# SCH_USB-PD_Power.net
KiCad netlist of a schematic drawn in Altium Designer
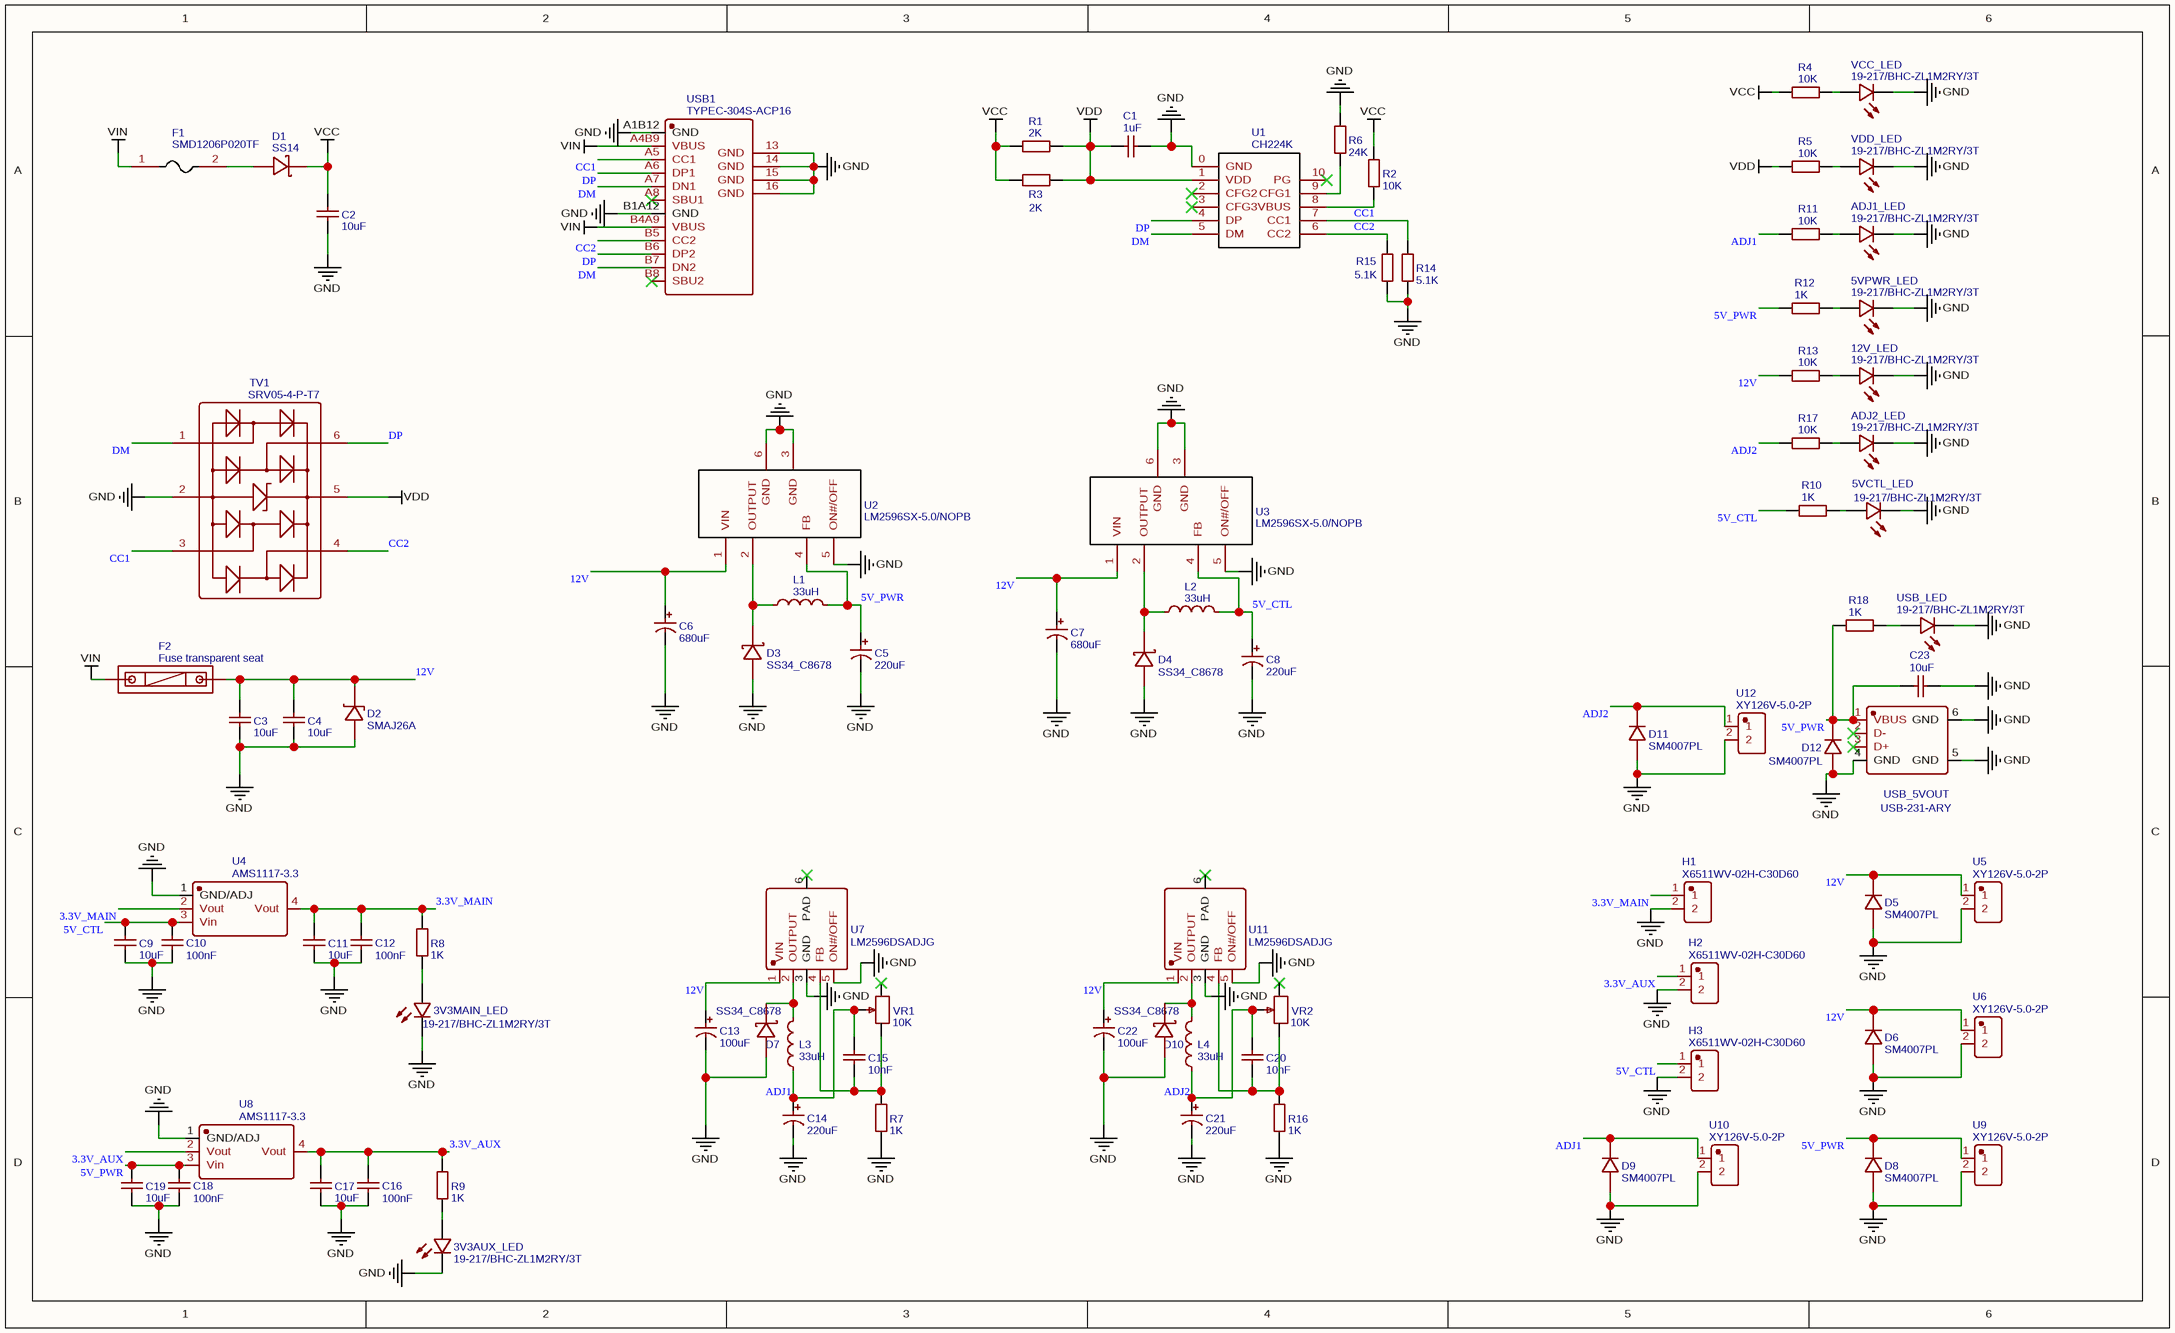
[diagram p0: SCH_USB-PD_Power.schdoc]

(export (version "E")
  (design (tool "Eeschema 10.0.6"))
  (components
    (comp (ref "3V3AUX_LED")
      (value "19-217/BHC-ZL1M2RY/3T")
      (fields (field (name "BOM_SUPPLIER PART") "C72041"))
      (libsource (lib "altium-import") (part "root_1_19-217/BHC-ZL1M2RY/3T_"))
    )
    (comp (ref "3V3MAIN_LED")
      (value "19-217/BHC-ZL1M2RY/3T")
      (fields (field (name "BOM_SUPPLIER PART") "C72041"))
      (libsource (lib "altium-import") (part "root_1_19-217/BHC-ZL1M2RY/3T_"))
    )
    (comp (ref "5VCTL_LED")
      (value "19-217/BHC-ZL1M2RY/3T")
      (fields (field (name "BOM_SUPPLIER PART") "C72041"))
      (libsource (lib "altium-import") (part "root_2_19-217/BHC-ZL1M2RY/3T_"))
    )
    (comp (ref "5VPWR_LED")
      (value "19-217/BHC-ZL1M2RY/3T")
      (fields (field (name "BOM_SUPPLIER PART") "C72041"))
      (libsource (lib "altium-import") (part "root_2_19-217/BHC-ZL1M2RY/3T_"))
    )
    (comp (ref "12V_LED")
      (value "19-217/BHC-ZL1M2RY/3T")
      (fields (field (name "BOM_SUPPLIER PART") "C72041"))
      (libsource (lib "altium-import") (part "root_2_19-217/BHC-ZL1M2RY/3T_"))
    )
    (comp (ref "ADJ1_LED")
      (value "19-217/BHC-ZL1M2RY/3T")
      (fields (field (name "BOM_SUPPLIER PART") "C72041"))
      (libsource (lib "altium-import") (part "root_2_19-217/BHC-ZL1M2RY/3T_"))
    )
    (comp (ref "ADJ2_LED")
      (value "19-217/BHC-ZL1M2RY/3T")
      (fields (field (name "BOM_SUPPLIER PART") "C72041"))
      (libsource (lib "altium-import") (part "root_2_19-217/BHC-ZL1M2RY/3T_"))
    )
    (comp (ref "C1")
      (value "1uF")
      (fields
        (field (name "BOM_MANUFACTURER PART") "CL21B105KBFNNNE")
        (field (name "BOM_SUPPLIER PART") "C28323")
      )
      (libsource (lib "altium-import") (part "root_0_1uF_"))
    )
    (comp (ref "C2")
      (value "10uF")
      (fields
        (field (name "BOM_MANUFACTURER PART") "CL21A106KAYNNNE")
        (field (name "BOM_SUPPLIER PART") "C15850")
      )
      (libsource (lib "altium-import") (part "root_1_10uF_"))
    )
    (comp (ref "C3")
      (value "10uF")
      (fields
        (field (name "BOM_MANUFACTURER PART") "CL21A106KAYNNNE")
        (field (name "BOM_SUPPLIER PART") "C15850")
      )
      (libsource (lib "altium-import") (part "root_1_10uF_"))
    )
    (comp (ref "C4")
      (value "10uF")
      (fields
        (field (name "BOM_MANUFACTURER PART") "CL21A106KAYNNNE")
        (field (name "BOM_SUPPLIER PART") "C15850")
      )
      (libsource (lib "altium-import") (part "root_1_10uF_"))
    )
    (comp (ref "C5")
      (value "220uF")
      (fields (field (name "BOM_MANUFACTURER PART") "220uf/35V") (field (name "BOM_SUPPLIER PART") "C2063"))
      (libsource (lib "altium-import") (part "root_3_220uF_"))
    )
    (comp (ref "C6")
      (value "680uF")
      (fields
        (field (name "BOM_MANUFACTURER PART") "NXA25V680UF10*16")
        (field (name "BOM_SUPPLIER PART") "C150380")
        (field (name "CONTRIBUTOR") "LCSC")
      )
      (libsource (lib "altium-import") (part "root_3_680uF_"))
    )
    (comp (ref "C7")
      (value "680uF")
      (fields
        (field (name "BOM_MANUFACTURER PART") "NXA25V680UF10*16")
        (field (name "BOM_SUPPLIER PART") "C150380")
        (field (name "CONTRIBUTOR") "LCSC")
      )
      (libsource (lib "altium-import") (part "root_3_680uF_"))
    )
    (comp (ref "C8")
      (value "220uF")
      (fields (field (name "BOM_MANUFACTURER PART") "220uf/35V") (field (name "BOM_SUPPLIER PART") "C2063"))
      (libsource (lib "altium-import") (part "root_3_220uF_"))
    )
    (comp (ref "C9")
      (value "10uF")
      (fields
        (field (name "BOM_MANUFACTURER PART") "CL21A106KAYNNNE")
        (field (name "BOM_SUPPLIER PART") "C15850")
      )
      (libsource (lib "altium-import") (part "root_1_10uF_"))
    )
    (comp (ref "C10")
      (value "100nF")
      (fields
        (field (name "BOM_MANUFACTURER PART") "CC0805KRX7R9BB104")
        (field (name "BOM_SUPPLIER PART") "C49678")
      )
      (libsource (lib "altium-import") (part "root_1_100nF_"))
    )
    (comp (ref "C11")
      (value "10uF")
      (fields
        (field (name "BOM_MANUFACTURER PART") "CL21A106KAYNNNE")
        (field (name "BOM_SUPPLIER PART") "C15850")
      )
      (libsource (lib "altium-import") (part "root_1_10uF_"))
    )
    (comp (ref "C12")
      (value "100nF")
      (fields
        (field (name "BOM_MANUFACTURER PART") "CC0805KRX7R9BB104")
        (field (name "BOM_SUPPLIER PART") "C49678")
      )
      (libsource (lib "altium-import") (part "root_1_100nF_"))
    )
    (comp (ref "C13")
      (value "100uF")
      (fields
        (field (name "BOM_MANUFACTURER PART") "100uF 63V 10*13")
        (field (name "BOM_SUPPLIER PART") "C45675")
      )
      (libsource (lib "altium-import") (part "root_3_100uF_"))
    )
    (comp (ref "C14")
      (value "220uF")
      (fields (field (name "BOM_MANUFACTURER PART") "220uf/35V") (field (name "BOM_SUPPLIER PART") "C2063"))
      (libsource (lib "altium-import") (part "root_3_220uF_"))
    )
    (comp (ref "C15")
      (value "10nF")
      (fields
        (field (name "BOM_MANUFACTURER PART") "CL21B103KBANNNC")
        (field (name "BOM_SUPPLIER PART") "C1710")
      )
      (libsource (lib "altium-import") (part "root_1_10nF_"))
    )
    (comp (ref "C16")
      (value "100nF")
      (fields
        (field (name "BOM_MANUFACTURER PART") "CC0805KRX7R9BB104")
        (field (name "BOM_SUPPLIER PART") "C49678")
      )
      (libsource (lib "altium-import") (part "root_1_100nF_"))
    )
    (comp (ref "C17")
      (value "10uF")
      (fields
        (field (name "BOM_MANUFACTURER PART") "CL21A106KAYNNNE")
        (field (name "BOM_SUPPLIER PART") "C15850")
      )
      (libsource (lib "altium-import") (part "root_1_10uF_"))
    )
    (comp (ref "C18")
      (value "100nF")
      (fields
        (field (name "BOM_MANUFACTURER PART") "CC0805KRX7R9BB104")
        (field (name "BOM_SUPPLIER PART") "C49678")
      )
      (libsource (lib "altium-import") (part "root_1_100nF_"))
    )
    (comp (ref "C19")
      (value "10uF")
      (fields
        (field (name "BOM_MANUFACTURER PART") "CL21A106KAYNNNE")
        (field (name "BOM_SUPPLIER PART") "C15850")
      )
      (libsource (lib "altium-import") (part "root_1_10uF_"))
    )
    (comp (ref "C20")
      (value "10nF")
      (fields
        (field (name "BOM_MANUFACTURER PART") "CL21B103KBANNNC")
        (field (name "BOM_SUPPLIER PART") "C1710")
      )
      (libsource (lib "altium-import") (part "root_1_10nF_"))
    )
    (comp (ref "C21")
      (value "220uF")
      (fields (field (name "BOM_MANUFACTURER PART") "220uf/35V") (field (name "BOM_SUPPLIER PART") "C2063"))
      (libsource (lib "altium-import") (part "root_3_220uF_"))
    )
    (comp (ref "C22")
      (value "100uF")
      (fields
        (field (name "BOM_MANUFACTURER PART") "100uF 63V 10*13")
        (field (name "BOM_SUPPLIER PART") "C45675")
      )
      (libsource (lib "altium-import") (part "root_3_100uF_"))
    )
    (comp (ref "C23")
      (value "10uF")
      (fields
        (field (name "BOM_MANUFACTURER PART") "CL21A106KAYNNNE")
        (field (name "BOM_SUPPLIER PART") "C15850")
      )
      (libsource (lib "altium-import") (part "root_0_10uF_"))
    )
    (comp (ref "D1")
      (value "SS14")
      (fields (field (name "BOM_SUPPLIER PART") "C2480"))
      (libsource (lib "altium-import") (part "root_2_SS14_"))
    )
    (comp (ref "D2")
      (value "SMAJ26A")
      (fields (field (name "BOM_SUPPLIER PART") "C49370"))
      (libsource (lib "altium-import") (part "root_3_SMAJ26A_"))
    )
    (comp (ref "D3")
      (value "SS34_C8678")
      (fields (field (name "BOM_MANUFACTURER PART") "SS34") (field (name "BOM_SUPPLIER PART") "C8678"))
      (libsource (lib "altium-import") (part "root_3_SS34_C8678_"))
    )
    (comp (ref "D4")
      (value "SS34_C8678")
      (fields (field (name "BOM_MANUFACTURER PART") "SS34") (field (name "BOM_SUPPLIER PART") "C8678"))
      (libsource (lib "altium-import") (part "root_3_SS34_C8678_"))
    )
    (comp (ref "D5")
      (value "SM4007PL")
      (fields (field (name "BOM_SUPPLIER PART") "C64898"))
      (libsource (lib "altium-import") (part "root_3_SM4007PL_"))
    )
    (comp (ref "D6")
      (value "SM4007PL")
      (fields (field (name "BOM_SUPPLIER PART") "C64898"))
      (libsource (lib "altium-import") (part "root_3_SM4007PL_"))
    )
    (comp (ref "D7")
      (value "SS34_C8678")
      (fields (field (name "BOM_MANUFACTURER PART") "SS34") (field (name "BOM_SUPPLIER PART") "C8678"))
      (libsource (lib "altium-import") (part "root_3_SS34_C8678_"))
    )
    (comp (ref "D8")
      (value "SM4007PL")
      (fields (field (name "BOM_SUPPLIER PART") "C64898"))
      (libsource (lib "altium-import") (part "root_3_SM4007PL_"))
    )
    (comp (ref "D9")
      (value "SM4007PL")
      (fields (field (name "BOM_SUPPLIER PART") "C64898"))
      (libsource (lib "altium-import") (part "root_3_SM4007PL_"))
    )
    (comp (ref "D10")
      (value "SS34_C8678")
      (fields (field (name "BOM_MANUFACTURER PART") "SS34") (field (name "BOM_SUPPLIER PART") "C8678"))
      (libsource (lib "altium-import") (part "root_3_SS34_C8678_"))
    )
    (comp (ref "D11")
      (value "SM4007PL")
      (fields (field (name "BOM_SUPPLIER PART") "C64898"))
      (libsource (lib "altium-import") (part "root_3_SM4007PL_"))
    )
    (comp (ref "D12")
      (value "SM4007PL")
      (fields (field (name "BOM_SUPPLIER PART") "C64898"))
      (libsource (lib "altium-import") (part "root_3_SM4007PL_"))
    )
    (comp (ref "F1")
      (value "SMD1206P020TF")
      (fields (field (name "BOM_SUPPLIER PART") "C20984"))
      (libsource (lib "altium-import") (part "root_0_SMD1206P020TF_"))
    )
    (comp (ref "F2")
      (value "Fuse transparent seat")
      (fields (field (name "BOM_SUPPLIER PART") "C58066"))
      (libsource (lib "altium-import") (part "root_0_Fuse transparent seat_"))
    )
    (comp (ref "H1")
      (value "X6511WV-02H-C30D60")
      (fields (field (name "BOM_SUPPLIER PART") "C706874") (field (name "CONTRIBUTOR") "LCSC"))
      (libsource (lib "altium-import") (part "root_0_X6511WV-02H-C30D60_"))
    )
    (comp (ref "H2")
      (value "X6511WV-02H-C30D60")
      (fields (field (name "BOM_SUPPLIER PART") "C706874") (field (name "CONTRIBUTOR") "LCSC"))
      (libsource (lib "altium-import") (part "root_0_X6511WV-02H-C30D60_"))
    )
    (comp (ref "H3")
      (value "X6511WV-02H-C30D60")
      (fields (field (name "BOM_SUPPLIER PART") "C706874") (field (name "CONTRIBUTOR") "LCSC"))
      (libsource (lib "altium-import") (part "root_0_X6511WV-02H-C30D60_"))
    )
    (comp (ref "L1")
      (value "33uH")
      (fields
        (field (name "BOM_SUPPLIER PART") "C169375")
        (field (name "BOM_MANUFACTURER PART") "SWRB1207S-330MT")
        (field (name "CONTRIBUTOR") "LCSC")
      )
      (libsource (lib "altium-import") (part "root_0_33uH_"))
    )
    (comp (ref "L2")
      (value "33uH")
      (fields
        (field (name "BOM_SUPPLIER PART") "C169375")
        (field (name "BOM_MANUFACTURER PART") "SWRB1207S-330MT")
        (field (name "CONTRIBUTOR") "LCSC")
      )
      (libsource (lib "altium-import") (part "root_0_33uH_"))
    )
    (comp (ref "L3")
      (value "33uH")
      (fields
        (field (name "BOM_SUPPLIER PART") "C169375")
        (field (name "BOM_MANUFACTURER PART") "SWRB1207S-330MT")
        (field (name "CONTRIBUTOR") "LCSC")
      )
      (libsource (lib "altium-import") (part "root_1_33uH_"))
    )
    (comp (ref "L4")
      (value "33uH")
      (fields
        (field (name "BOM_SUPPLIER PART") "C169375")
        (field (name "BOM_MANUFACTURER PART") "SWRB1207S-330MT")
        (field (name "CONTRIBUTOR") "LCSC")
      )
      (libsource (lib "altium-import") (part "root_1_33uH_"))
    )
    (comp (ref "R1")
      (value "2K")
      (fields
        (field (name "BOM_MANUFACTURER PART") "0805W8F2001T5E")
        (field (name "BOM_SUPPLIER PART") "C17604")
      )
      (libsource (lib "altium-import") (part "root_0_2K_"))
    )
    (comp (ref "R2")
      (value "10K")
      (fields
        (field (name "BOM_MANUFACTURER PART") "0805W8F1002T5E")
        (field (name "BOM_SUPPLIER PART") "C17414")
      )
      (libsource (lib "altium-import") (part "root_1_10K_"))
    )
    (comp (ref "R3")
      (value "2K")
      (fields
        (field (name "BOM_MANUFACTURER PART") "0805W8F2001T5E")
        (field (name "BOM_SUPPLIER PART") "C17604")
      )
      (libsource (lib "altium-import") (part "root_0_2K_"))
    )
    (comp (ref "R4")
      (value "10K")
      (fields
        (field (name "BOM_MANUFACTURER PART") "0805W8F1002T5E")
        (field (name "BOM_SUPPLIER PART") "C17414")
      )
      (libsource (lib "altium-import") (part "root_2_10K_"))
    )
    (comp (ref "R5")
      (value "10K")
      (fields
        (field (name "BOM_MANUFACTURER PART") "0805W8F1002T5E")
        (field (name "BOM_SUPPLIER PART") "C17414")
      )
      (libsource (lib "altium-import") (part "root_2_10K_"))
    )
    (comp (ref "R6")
      (value "24K")
      (fields
        (field (name "BOM_MANUFACTURER PART") "0805W8F2402T5E")
        (field (name "BOM_SUPPLIER PART") "C17575")
      )
      (libsource (lib "altium-import") (part "root_1_24K_"))
    )
    (comp (ref "R7")
      (value "1K")
      (fields
        (field (name "BOM_MANUFACTURER PART") "0805W8F1001T5E")
        (field (name "BOM_SUPPLIER PART") "C17513")
      )
      (libsource (lib "altium-import") (part "root_1_1K_"))
    )
    (comp (ref "R8")
      (value "1K")
      (fields
        (field (name "BOM_MANUFACTURER PART") "0805W8F1001T5E")
        (field (name "BOM_SUPPLIER PART") "C17513")
      )
      (libsource (lib "altium-import") (part "root_1_1K_"))
    )
    (comp (ref "R9")
      (value "1K")
      (fields
        (field (name "BOM_MANUFACTURER PART") "0805W8F1001T5E")
        (field (name "BOM_SUPPLIER PART") "C17513")
      )
      (libsource (lib "altium-import") (part "root_1_1K_"))
    )
    (comp (ref "R10")
      (value "1K")
      (fields
        (field (name "BOM_MANUFACTURER PART") "0805W8F1001T5E")
        (field (name "BOM_SUPPLIER PART") "C17513")
      )
      (libsource (lib "altium-import") (part "root_2_1K_"))
    )
    (comp (ref "R11")
      (value "10K")
      (fields
        (field (name "BOM_MANUFACTURER PART") "0805W8F1002T5E")
        (field (name "BOM_SUPPLIER PART") "C17414")
      )
      (libsource (lib "altium-import") (part "root_2_10K_"))
    )
    (comp (ref "R12")
      (value "1K")
      (fields
        (field (name "BOM_MANUFACTURER PART") "0805W8F1001T5E")
        (field (name "BOM_SUPPLIER PART") "C17513")
      )
      (libsource (lib "altium-import") (part "root_2_1K_"))
    )
    (comp (ref "R13")
      (value "10K")
      (fields
        (field (name "BOM_MANUFACTURER PART") "0805W8F1002T5E")
        (field (name "BOM_SUPPLIER PART") "C17414")
      )
      (libsource (lib "altium-import") (part "root_2_10K_"))
    )
    (comp (ref "R14")
      (value "5.1K")
      (fields
        (field (name "BOM_MANUFACTURER PART") "0805W8F5101T5E")
        (field (name "BOM_SUPPLIER PART") "C27834")
      )
      (libsource (lib "altium-import") (part "root_1_5.1K_"))
    )
    (comp (ref "R15")
      (value "5.1K")
      (fields
        (field (name "BOM_MANUFACTURER PART") "0805W8F5101T5E")
        (field (name "BOM_SUPPLIER PART") "C27834")
      )
      (libsource (lib "altium-import") (part "root_1_5.1K_"))
    )
    (comp (ref "R16")
      (value "1K")
      (fields
        (field (name "BOM_MANUFACTURER PART") "0805W8F1001T5E")
        (field (name "BOM_SUPPLIER PART") "C17513")
      )
      (libsource (lib "altium-import") (part "root_1_1K_"))
    )
    (comp (ref "R17")
      (value "10K")
      (fields
        (field (name "BOM_MANUFACTURER PART") "0805W8F1002T5E")
        (field (name "BOM_SUPPLIER PART") "C17414")
      )
      (libsource (lib "altium-import") (part "root_2_10K_"))
    )
    (comp (ref "R18")
      (value "1K")
      (fields
        (field (name "BOM_MANUFACTURER PART") "0805W8F1001T5E")
        (field (name "BOM_SUPPLIER PART") "C17513")
      )
      (libsource (lib "altium-import") (part "root_0_1K_"))
    )
    (comp (ref "TV1")
      (value "SRV05-4-P-T7")
      (fields (field (name "BOM_SUPPLIER PART") "C85364"))
      (libsource (lib "altium-import") (part "root_2_SRV05-4-P-T7_"))
    )
    (comp (ref "U1")
      (value "CH224K")
      (fields (field (name "CONTRIBUTOR") "hans_1024"))
      (libsource (lib "altium-import") (part "root_0_CH224K_"))
    )
    (comp (ref "U2")
      (value "LM2596SX-5.0/NOPB")
      (fields (field (name "BOM_SUPPLIER PART") "C10002"))
      (libsource (lib "altium-import") (part "root_3_LM2596SX-5.0/NOPB_"))
    )
    (comp (ref "U3")
      (value "LM2596SX-5.0/NOPB")
      (fields (field (name "BOM_SUPPLIER PART") "C10002"))
      (libsource (lib "altium-import") (part "root_3_LM2596SX-5.0/NOPB_"))
    )
    (comp (ref "U4")
      (value "AMS1117-3.3")
      (fields (field (name "BOM_SUPPLIER PART") "C6186"))
      (libsource (lib "altium-import") (part "root_0_AMS1117-3.3_"))
    )
    (comp (ref "U5")
      (value "XY126V-5.0-2P")
      (fields (field (name "BOM_SUPPLIER PART") "C557646") (field (name "CONTRIBUTOR") "LCSC"))
      (libsource (lib "altium-import") (part "root_0_XY126V-5.0-2P_"))
    )
    (comp (ref "U6")
      (value "XY126V-5.0-2P")
      (fields (field (name "BOM_SUPPLIER PART") "C557646") (field (name "CONTRIBUTOR") "LCSC"))
      (libsource (lib "altium-import") (part "root_0_XY126V-5.0-2P_"))
    )
    (comp (ref "U7")
      (value "LM2596DSADJG")
      (fields (field (name "BOM_SUPPLIER PART") "C92134"))
      (libsource (lib "altium-import") (part "root_1_LM2596DSADJG_"))
    )
    (comp (ref "U8")
      (value "AMS1117-3.3")
      (fields (field (name "BOM_SUPPLIER PART") "C6186"))
      (libsource (lib "altium-import") (part "root_0_AMS1117-3.3_"))
    )
    (comp (ref "U9")
      (value "XY126V-5.0-2P")
      (fields (field (name "BOM_SUPPLIER PART") "C557646") (field (name "CONTRIBUTOR") "LCSC"))
      (libsource (lib "altium-import") (part "root_0_XY126V-5.0-2P_"))
    )
    (comp (ref "U10")
      (value "XY126V-5.0-2P")
      (fields (field (name "BOM_SUPPLIER PART") "C557646") (field (name "CONTRIBUTOR") "LCSC"))
      (libsource (lib "altium-import") (part "root_0_XY126V-5.0-2P_"))
    )
    (comp (ref "U11")
      (value "LM2596DSADJG")
      (fields (field (name "BOM_SUPPLIER PART") "C92134"))
      (libsource (lib "altium-import") (part "root_1_LM2596DSADJG_"))
    )
    (comp (ref "U12")
      (value "XY126V-5.0-2P")
      (fields (field (name "BOM_SUPPLIER PART") "C557646") (field (name "CONTRIBUTOR") "LCSC"))
      (libsource (lib "altium-import") (part "root_0_XY126V-5.0-2P_"))
    )
    (comp (ref "USB1")
      (value "TYPEC-304S-ACP16")
      (fields (field (name "BOM_SUPPLIER PART") "C720630") (field (name "CONTRIBUTOR") "LCSC"))
      (libsource (lib "altium-import") (part "root_0_TYPEC-304S-ACP16_"))
    )
    (comp (ref "USB_5VOUT")
      (value "USB-231-ARY")
      (fields (field (name "BOM_SUPPLIER PART") "C720525") (field (name "CONTRIBUTOR") "LCSC"))
      (libsource (lib "altium-import") (part "root_0_USB-231-ARY_"))
    )
    (comp (ref "USB_LED")
      (value "19-217/BHC-ZL1M2RY/3T")
      (fields (field (name "BOM_SUPPLIER PART") "C72041"))
      (libsource (lib "altium-import") (part "root_2_19-217/BHC-ZL1M2RY/3T_"))
    )
    (comp (ref "VCC_LED")
      (value "19-217/BHC-ZL1M2RY/3T")
      (fields (field (name "BOM_SUPPLIER PART") "C72041"))
      (libsource (lib "altium-import") (part "root_2_19-217/BHC-ZL1M2RY/3T_"))
    )
    (comp (ref "VDD_LED")
      (value "19-217/BHC-ZL1M2RY/3T")
      (fields (field (name "BOM_SUPPLIER PART") "C72041"))
      (libsource (lib "altium-import") (part "root_2_19-217/BHC-ZL1M2RY/3T_"))
    )
    (comp (ref "VR1")
      (value "10K")
      (fields
        (field (name "BOM_MANUFACTURER PART") "3362P-1-103LF")
        (field (name "BOM_SUPPLIER PART") "C58159")
      )
      (libsource (lib "altium-import") (part "root_0_10K_"))
    )
    (comp (ref "VR2")
      (value "10K")
      (fields
        (field (name "BOM_MANUFACTURER PART") "3362P-1-103LF")
        (field (name "BOM_SUPPLIER PART") "C58159")
      )
      (libsource (lib "altium-import") (part "root_0_10K_"))
    )
  )
  (nets
    (net (code "1") (name "/3.3V_AUX") (class "Default")
      (node (ref "C16") (pin "2") (pinfunction "2_2") (pintype "passive"))
      (node (ref "C17") (pin "2") (pinfunction "2_2") (pintype "passive"))
      (node (ref "H2") (pin "1") (pinfunction "1_1") (pintype "passive"))
      (node (ref "R9") (pin "2") (pinfunction "2_2") (pintype "passive"))
      (node (ref "U8") (pin "2") (pinfunction "Vout_2") (pintype "passive"))
      (node (ref "U8") (pin "4") (pinfunction "Vout_4") (pintype "passive"))
    )
    (net (code "2") (name "/3.3V_MAIN") (class "Default")
      (node (ref "C11") (pin "2") (pinfunction "2_2") (pintype "passive"))
      (node (ref "C12") (pin "2") (pinfunction "2_2") (pintype "passive"))
      (node (ref "H1") (pin "1") (pinfunction "1_1") (pintype "passive"))
      (node (ref "R8") (pin "2") (pinfunction "2_2") (pintype "passive"))
      (node (ref "U4") (pin "2") (pinfunction "Vout_2") (pintype "passive"))
      (node (ref "U4") (pin "4") (pinfunction "Vout_4") (pintype "passive"))
    )
    (net (code "3") (name "/5V_CTL") (class "Default")
      (node (ref "C10") (pin "2") (pinfunction "2_2") (pintype "passive"))
      (node (ref "C8") (pin "1") (pinfunction "1_1") (pintype "passive"))
      (node (ref "C9") (pin "2") (pinfunction "2_2") (pintype "passive"))
      (node (ref "H3") (pin "1") (pinfunction "1_1") (pintype "passive"))
      (node (ref "L2") (pin "2") (pinfunction "2_2") (pintype "passive"))
      (node (ref "R10") (pin "2") (pinfunction "2_2") (pintype "passive"))
      (node (ref "U3") (pin "4") (pinfunction "FB_4") (pintype "passive"))
      (node (ref "U4") (pin "3") (pinfunction "Vin_3") (pintype "passive"))
    )
    (net (code "4") (name "/5V_PWR") (class "Default")
      (node (ref "C18") (pin "2") (pinfunction "2_2") (pintype "passive"))
      (node (ref "C19") (pin "2") (pinfunction "2_2") (pintype "passive"))
      (node (ref "C23") (pin "1") (pinfunction "1_1") (pintype "passive"))
      (node (ref "C5") (pin "1") (pinfunction "1_1") (pintype "passive"))
      (node (ref "D12") (pin "1") (pinfunction "C_1") (pintype "passive"))
      (node (ref "D8") (pin "1") (pinfunction "C_1") (pintype "passive"))
      (node (ref "L1") (pin "2") (pinfunction "2_2") (pintype "passive"))
      (node (ref "R12") (pin "2") (pinfunction "2_2") (pintype "passive"))
      (node (ref "R18") (pin "1") (pinfunction "1_1") (pintype "passive"))
      (node (ref "U2") (pin "4") (pinfunction "FB_4") (pintype "passive"))
      (node (ref "U8") (pin "3") (pinfunction "Vin_3") (pintype "passive"))
      (node (ref "U9") (pin "1") (pinfunction "1_1") (pintype "passive"))
      (node (ref "USB_5VOUT") (pin "1") (pinfunction "VBUS_1") (pintype "passive"))
    )
    (net (code "5") (name "/12V") (class "Default")
      (node (ref "C13") (pin "1") (pinfunction "1_1") (pintype "passive"))
      (node (ref "C22") (pin "1") (pinfunction "1_1") (pintype "passive"))
      (node (ref "C3") (pin "2") (pinfunction "2_2") (pintype "passive"))
      (node (ref "C4") (pin "2") (pinfunction "2_2") (pintype "passive"))
      (node (ref "C6") (pin "1") (pinfunction "1_1") (pintype "passive"))
      (node (ref "C7") (pin "1") (pinfunction "1_1") (pintype "passive"))
      (node (ref "D2") (pin "1") (pinfunction "K_1") (pintype "passive"))
      (node (ref "D5") (pin "1") (pinfunction "C_1") (pintype "passive"))
      (node (ref "D6") (pin "1") (pinfunction "C_1") (pintype "passive"))
      (node (ref "F2") (pin "2") (pinfunction "2_2") (pintype "passive"))
      (node (ref "R13") (pin "2") (pinfunction "2_2") (pintype "passive"))
      (node (ref "U11") (pin "1") (pinfunction "VIN_1") (pintype "passive"))
      (node (ref "U2") (pin "1") (pinfunction "VIN_1") (pintype "passive"))
      (node (ref "U3") (pin "1") (pinfunction "VIN_1") (pintype "passive"))
      (node (ref "U5") (pin "1") (pinfunction "1_1") (pintype "passive"))
      (node (ref "U6") (pin "1") (pinfunction "1_1") (pintype "passive"))
      (node (ref "U7") (pin "1") (pinfunction "VIN_1") (pintype "passive"))
    )
    (net (code "6") (name "/ADJ1") (class "Default")
      (node (ref "C14") (pin "1") (pinfunction "1_1") (pintype "passive"))
      (node (ref "C15") (pin "2") (pinfunction "2_2") (pintype "passive"))
      (node (ref "D9") (pin "1") (pinfunction "C_1") (pintype "passive"))
      (node (ref "L3") (pin "1") (pinfunction "1_1") (pintype "passive"))
      (node (ref "R11") (pin "2") (pinfunction "2_2") (pintype "passive"))
      (node (ref "U10") (pin "1") (pinfunction "1_1") (pintype "passive"))
      (node (ref "VR1") (pin "2") (pinfunction "2_2") (pintype "passive"))
    )
    (net (code "7") (name "/ADJ2") (class "Default")
      (node (ref "C20") (pin "2") (pinfunction "2_2") (pintype "passive"))
      (node (ref "C21") (pin "1") (pinfunction "1_1") (pintype "passive"))
      (node (ref "D11") (pin "1") (pinfunction "C_1") (pintype "passive"))
      (node (ref "L4") (pin "1") (pinfunction "1_1") (pintype "passive"))
      (node (ref "R17") (pin "2") (pinfunction "2_2") (pintype "passive"))
      (node (ref "U12") (pin "1") (pinfunction "1_1") (pintype "passive"))
      (node (ref "VR2") (pin "2") (pinfunction "2_2") (pintype "passive"))
    )
    (net (code "8") (name "/CC1") (class "Default")
      (node (ref "R14") (pin "2") (pinfunction "2_2") (pintype "passive"))
      (node (ref "TV1") (pin "3") (pinfunction "3_3") (pintype "passive"))
      (node (ref "U1") (pin "7") (pinfunction "CC1_7") (pintype "passive"))
      (node (ref "USB1") (pin "A5") (pinfunction "CC1_A5") (pintype "passive"))
    )
    (net (code "9") (name "/CC2") (class "Default")
      (node (ref "R15") (pin "2") (pinfunction "2_2") (pintype "passive"))
      (node (ref "TV1") (pin "4") (pinfunction "4_4") (pintype "passive"))
      (node (ref "U1") (pin "6") (pinfunction "CC2_6") (pintype "passive"))
      (node (ref "USB1") (pin "B5") (pinfunction "CC2_B5") (pintype "passive"))
    )
    (net (code "10") (name "/DM") (class "Default")
      (node (ref "TV1") (pin "1") (pinfunction "1_1") (pintype "passive"))
      (node (ref "U1") (pin "5") (pinfunction "DM_5") (pintype "passive"))
      (node (ref "USB1") (pin "A7") (pinfunction "DN1_A7") (pintype "passive"))
      (node (ref "USB1") (pin "B7") (pinfunction "DN2_B7") (pintype "passive"))
    )
    (net (code "11") (name "/DP") (class "Default")
      (node (ref "TV1") (pin "6") (pinfunction "6_6") (pintype "passive"))
      (node (ref "U1") (pin "4") (pinfunction "DP_4") (pintype "passive"))
      (node (ref "USB1") (pin "A6") (pinfunction "DP1_A6") (pintype "passive"))
      (node (ref "USB1") (pin "B6") (pinfunction "DP2_B6") (pintype "passive"))
    )
    (net (code "12") (name "GND") (class "Default")
      (node (ref "12V_LED") (pin "2") (pinfunction "C_2") (pintype "passive"))
      (node (ref "3V3AUX_LED") (pin "2") (pinfunction "C_2") (pintype "passive"))
      (node (ref "3V3MAIN_LED") (pin "2") (pinfunction "C_2") (pintype "passive"))
      (node (ref "5VCTL_LED") (pin "2") (pinfunction "C_2") (pintype "passive"))
      (node (ref "5VPWR_LED") (pin "2") (pinfunction "C_2") (pintype "passive"))
      (node (ref "ADJ1_LED") (pin "2") (pinfunction "C_2") (pintype "passive"))
      (node (ref "ADJ2_LED") (pin "2") (pinfunction "C_2") (pintype "passive"))
      (node (ref "C1") (pin "2") (pinfunction "2_2") (pintype "passive"))
      (node (ref "C10") (pin "1") (pinfunction "1_1") (pintype "passive"))
      (node (ref "C11") (pin "1") (pinfunction "1_1") (pintype "passive"))
      (node (ref "C12") (pin "1") (pinfunction "1_1") (pintype "passive"))
      (node (ref "C13") (pin "2") (pinfunction "2_2") (pintype "passive"))
      (node (ref "C14") (pin "2") (pinfunction "2_2") (pintype "passive"))
      (node (ref "C16") (pin "1") (pinfunction "1_1") (pintype "passive"))
      (node (ref "C17") (pin "1") (pinfunction "1_1") (pintype "passive"))
      (node (ref "C18") (pin "1") (pinfunction "1_1") (pintype "passive"))
      (node (ref "C19") (pin "1") (pinfunction "1_1") (pintype "passive"))
      (node (ref "C2") (pin "1") (pinfunction "1_1") (pintype "passive"))
      (node (ref "C21") (pin "2") (pinfunction "2_2") (pintype "passive"))
      (node (ref "C22") (pin "2") (pinfunction "2_2") (pintype "passive"))
      (node (ref "C23") (pin "2") (pinfunction "2_2") (pintype "passive"))
      (node (ref "C3") (pin "1") (pinfunction "1_1") (pintype "passive"))
      (node (ref "C4") (pin "1") (pinfunction "1_1") (pintype "passive"))
      (node (ref "C5") (pin "2") (pinfunction "2_2") (pintype "passive"))
      (node (ref "C6") (pin "2") (pinfunction "2_2") (pintype "passive"))
      (node (ref "C7") (pin "2") (pinfunction "2_2") (pintype "passive"))
      (node (ref "C8") (pin "2") (pinfunction "2_2") (pintype "passive"))
      (node (ref "C9") (pin "1") (pinfunction "1_1") (pintype "passive"))
      (node (ref "D10") (pin "2") (pinfunction "A_2") (pintype "passive"))
      (node (ref "D11") (pin "2") (pinfunction "A_2") (pintype "passive"))
      (node (ref "D12") (pin "2") (pinfunction "A_2") (pintype "passive"))
      (node (ref "D2") (pin "2") (pinfunction "A_2") (pintype "passive"))
      (node (ref "D3") (pin "2") (pinfunction "A_2") (pintype "passive"))
      (node (ref "D4") (pin "2") (pinfunction "A_2") (pintype "passive"))
      (node (ref "D5") (pin "2") (pinfunction "A_2") (pintype "passive"))
      (node (ref "D6") (pin "2") (pinfunction "A_2") (pintype "passive"))
      (node (ref "D7") (pin "2") (pinfunction "A_2") (pintype "passive"))
      (node (ref "D8") (pin "2") (pinfunction "A_2") (pintype "passive"))
      (node (ref "D9") (pin "2") (pinfunction "A_2") (pintype "passive"))
      (node (ref "H1") (pin "2") (pinfunction "2_2") (pintype "passive"))
      (node (ref "H2") (pin "2") (pinfunction "2_2") (pintype "passive"))
      (node (ref "H3") (pin "2") (pinfunction "2_2") (pintype "passive"))
      (node (ref "R14") (pin "1") (pinfunction "1_1") (pintype "passive"))
      (node (ref "R15") (pin "1") (pinfunction "1_1") (pintype "passive"))
      (node (ref "R16") (pin "1") (pinfunction "1_1") (pintype "passive"))
      (node (ref "R6") (pin "2") (pinfunction "2_2") (pintype "passive"))
      (node (ref "R7") (pin "1") (pinfunction "1_1") (pintype "passive"))
      (node (ref "TV1") (pin "2") (pinfunction "2_2") (pintype "passive"))
      (node (ref "U1") (pin "0") (pinfunction "GND_0") (pintype "passive"))
      (node (ref "U10") (pin "2") (pinfunction "2_2") (pintype "passive"))
      (node (ref "U11") (pin "3") (pinfunction "GND_3") (pintype "passive"))
      (node (ref "U11") (pin "5") (pinfunction "ON#/OFF_5") (pintype "passive"))
      (node (ref "U12") (pin "2") (pinfunction "2_2") (pintype "passive"))
      (node (ref "U2") (pin "3") (pinfunction "GND_3") (pintype "passive"))
      (node (ref "U2") (pin "5") (pinfunction "ON#/OFF_5") (pintype "passive"))
      (node (ref "U2") (pin "6") (pinfunction "GND_6") (pintype "passive"))
      (node (ref "U3") (pin "3") (pinfunction "GND_3") (pintype "passive"))
      (node (ref "U3") (pin "5") (pinfunction "ON#/OFF_5") (pintype "passive"))
      (node (ref "U3") (pin "6") (pinfunction "GND_6") (pintype "passive"))
      (node (ref "U4") (pin "1") (pinfunction "GND/ADJ_1") (pintype "passive"))
      (node (ref "U5") (pin "2") (pinfunction "2_2") (pintype "passive"))
      (node (ref "U6") (pin "2") (pinfunction "2_2") (pintype "passive"))
      (node (ref "U7") (pin "3") (pinfunction "GND_3") (pintype "passive"))
      (node (ref "U7") (pin "5") (pinfunction "ON#/OFF_5") (pintype "passive"))
      (node (ref "U8") (pin "1") (pinfunction "GND/ADJ_1") (pintype "passive"))
      (node (ref "U9") (pin "2") (pinfunction "2_2") (pintype "passive"))
      (node (ref "USB1") (pin "13") (pinfunction "GND_13") (pintype "passive"))
      (node (ref "USB1") (pin "14") (pinfunction "GND_14") (pintype "passive"))
      (node (ref "USB1") (pin "15") (pinfunction "GND_15") (pintype "passive"))
      (node (ref "USB1") (pin "16") (pinfunction "GND_16") (pintype "passive"))
      (node (ref "USB1") (pin "A1B12") (pinfunction "GND_A1B12") (pintype "passive"))
      (node (ref "USB1") (pin "B1A12") (pinfunction "GND_B1A12") (pintype "passive"))
      (node (ref "USB_5VOUT") (pin "4") (pinfunction "GND_4") (pintype "passive"))
      (node (ref "USB_5VOUT") (pin "5") (pinfunction "GND_5") (pintype "passive"))
      (node (ref "USB_5VOUT") (pin "6") (pinfunction "GND_6") (pintype "passive"))
      (node (ref "USB_LED") (pin "2") (pinfunction "C_2") (pintype "passive"))
      (node (ref "VCC_LED") (pin "2") (pinfunction "C_2") (pintype "passive"))
      (node (ref "VDD_LED") (pin "2") (pinfunction "C_2") (pintype "passive"))
    )
    (net (code "13") (name "Net-(3V3AUX_LED-A)") (class "Default")
      (node (ref "3V3AUX_LED") (pin "1") (pinfunction "A_1") (pintype "passive"))
      (node (ref "R9") (pin "1") (pinfunction "1_1") (pintype "passive"))
    )
    (net (code "14") (name "Net-(3V3MAIN_LED-A)") (class "Default")
      (node (ref "3V3MAIN_LED") (pin "1") (pinfunction "A_1") (pintype "passive"))
      (node (ref "R8") (pin "1") (pinfunction "1_1") (pintype "passive"))
    )
    (net (code "15") (name "Net-(5VCTL_LED-A)") (class "Default")
      (node (ref "5VCTL_LED") (pin "1") (pinfunction "A_1") (pintype "passive"))
      (node (ref "R10") (pin "1") (pinfunction "1_1") (pintype "passive"))
    )
    (net (code "16") (name "Net-(5VPWR_LED-A)") (class "Default")
      (node (ref "5VPWR_LED") (pin "1") (pinfunction "A_1") (pintype "passive"))
      (node (ref "R12") (pin "1") (pinfunction "1_1") (pintype "passive"))
    )
    (net (code "17") (name "Net-(12V_LED-A)") (class "Default")
      (node (ref "12V_LED") (pin "1") (pinfunction "A_1") (pintype "passive"))
      (node (ref "R13") (pin "1") (pinfunction "1_1") (pintype "passive"))
    )
    (net (code "18") (name "Net-(ADJ1_LED-A)") (class "Default")
      (node (ref "ADJ1_LED") (pin "1") (pinfunction "A_1") (pintype "passive"))
      (node (ref "R11") (pin "1") (pinfunction "1_1") (pintype "passive"))
    )
    (net (code "19") (name "Net-(ADJ2_LED-A)") (class "Default")
      (node (ref "ADJ2_LED") (pin "1") (pinfunction "A_1") (pintype "passive"))
      (node (ref "R17") (pin "1") (pinfunction "1_1") (pintype "passive"))
    )
    (net (code "20") (name "Net-(D1-A)") (class "Default")
      (node (ref "D1") (pin "2") (pinfunction "A_2") (pintype "passive"))
      (node (ref "F1") (pin "2") (pinfunction "2_2") (pintype "passive"))
    )
    (net (code "21") (name "Net-(D3-K)") (class "Default")
      (node (ref "D3") (pin "1") (pinfunction "K_1") (pintype "passive"))
      (node (ref "L1") (pin "1") (pinfunction "1_1") (pintype "passive"))
      (node (ref "U2") (pin "2") (pinfunction "OUTPUT_2") (pintype "passive"))
    )
    (net (code "22") (name "Net-(D4-K)") (class "Default")
      (node (ref "D4") (pin "1") (pinfunction "K_1") (pintype "passive"))
      (node (ref "L2") (pin "1") (pinfunction "1_1") (pintype "passive"))
      (node (ref "U3") (pin "2") (pinfunction "OUTPUT_2") (pintype "passive"))
    )
    (net (code "23") (name "Net-(D7-K)") (class "Default")
      (node (ref "D7") (pin "1") (pinfunction "K_1") (pintype "passive"))
      (node (ref "L3") (pin "2") (pinfunction "2_2") (pintype "passive"))
      (node (ref "U7") (pin "2") (pinfunction "OUTPUT_2") (pintype "passive"))
    )
    (net (code "24") (name "Net-(D10-K)") (class "Default")
      (node (ref "D10") (pin "1") (pinfunction "K_1") (pintype "passive"))
      (node (ref "L4") (pin "2") (pinfunction "2_2") (pintype "passive"))
      (node (ref "U11") (pin "2") (pinfunction "OUTPUT_2") (pintype "passive"))
    )
    (net (code "25") (name "Net-(U1-CFG1)") (class "Default")
      (node (ref "R6") (pin "1") (pinfunction "1_1") (pintype "passive"))
      (node (ref "U1") (pin "9") (pinfunction "CFG1_9") (pintype "passive"))
    )
    (net (code "26") (name "Net-(U1-VBUS)") (class "Default")
      (node (ref "R2") (pin "1") (pinfunction "1_1") (pintype "passive"))
      (node (ref "U1") (pin "8") (pinfunction "VBUS_8") (pintype "passive"))
    )
    (net (code "27") (name "Net-(U7-FB)") (class "Default")
      (node (ref "C15") (pin "1") (pinfunction "1_1") (pintype "passive"))
      (node (ref "R7") (pin "2") (pinfunction "2_2") (pintype "passive"))
      (node (ref "U7") (pin "4") (pinfunction "FB_4") (pintype "passive"))
      (node (ref "VR1") (pin "3") (pinfunction "3_3") (pintype "passive"))
    )
    (net (code "28") (name "Net-(U11-FB)") (class "Default")
      (node (ref "C20") (pin "1") (pinfunction "1_1") (pintype "passive"))
      (node (ref "R16") (pin "2") (pinfunction "2_2") (pintype "passive"))
      (node (ref "U11") (pin "4") (pinfunction "FB_4") (pintype "passive"))
      (node (ref "VR2") (pin "3") (pinfunction "3_3") (pintype "passive"))
    )
    (net (code "29") (name "Net-(USB_LED-A)") (class "Default")
      (node (ref "R18") (pin "2") (pinfunction "2_2") (pintype "passive"))
      (node (ref "USB_LED") (pin "1") (pinfunction "A_1") (pintype "passive"))
    )
    (net (code "30") (name "Net-(VCC_LED-A)") (class "Default")
      (node (ref "R4") (pin "1") (pinfunction "1_1") (pintype "passive"))
      (node (ref "VCC_LED") (pin "1") (pinfunction "A_1") (pintype "passive"))
    )
    (net (code "31") (name "Net-(VDD_LED-A)") (class "Default")
      (node (ref "R5") (pin "1") (pinfunction "1_1") (pintype "passive"))
      (node (ref "VDD_LED") (pin "1") (pinfunction "A_1") (pintype "passive"))
    )
    (net (code "32") (name "VCC") (class "Default")
      (node (ref "C2") (pin "2") (pinfunction "2_2") (pintype "passive"))
      (node (ref "D1") (pin "1") (pinfunction "K_1") (pintype "passive"))
      (node (ref "R1") (pin "1") (pinfunction "1_1") (pintype "passive"))
      (node (ref "R2") (pin "2") (pinfunction "2_2") (pintype "passive"))
      (node (ref "R3") (pin "1") (pinfunction "1_1") (pintype "passive"))
      (node (ref "R4") (pin "2") (pinfunction "2_2") (pintype "passive"))
    )
    (net (code "33") (name "VDD") (class "Default")
      (node (ref "C1") (pin "1") (pinfunction "1_1") (pintype "passive"))
      (node (ref "R1") (pin "2") (pinfunction "2_2") (pintype "passive"))
      (node (ref "R3") (pin "2") (pinfunction "2_2") (pintype "passive"))
      (node (ref "R5") (pin "2") (pinfunction "2_2") (pintype "passive"))
      (node (ref "TV1") (pin "5") (pinfunction "5_5") (pintype "passive"))
      (node (ref "U1") (pin "1") (pinfunction "VDD_1") (pintype "passive"))
    )
    (net (code "34") (name "VIN") (class "Default")
      (node (ref "F1") (pin "1") (pinfunction "1_1") (pintype "passive"))
      (node (ref "F2") (pin "1") (pinfunction "1_1") (pintype "passive"))
      (node (ref "USB1") (pin "A4B9") (pinfunction "VBUS_A4B9") (pintype "passive"))
      (node (ref "USB1") (pin "B4A9") (pinfunction "VBUS_B4A9") (pintype "passive"))
    )
    (net (code "35") (name "unconnected-(U1-CFG2-Pad2)") (class "Default")
      (node (ref "U1") (pin "2") (pinfunction "CFG2_2") (pintype "passive+no_connect"))
    )
    (net (code "36") (name "unconnected-(U1-CFG3-Pad3)") (class "Default")
      (node (ref "U1") (pin "3") (pinfunction "CFG3_3") (pintype "passive+no_connect"))
    )
    (net (code "37") (name "unconnected-(U1-PG-Pad10)") (class "Default")
      (node (ref "U1") (pin "10") (pinfunction "PG_10") (pintype "passive+no_connect"))
    )
    (net (code "38") (name "unconnected-(U7-PAD-Pad6)") (class "Default")
      (node (ref "U7") (pin "6") (pinfunction "PAD_6") (pintype "passive+no_connect"))
    )
    (net (code "39") (name "unconnected-(U11-PAD-Pad6)") (class "Default")
      (node (ref "U11") (pin "6") (pinfunction "PAD_6") (pintype "passive+no_connect"))
    )
    (net (code "40") (name "unconnected-(USB1-SBU1-PadA8)") (class "Default")
      (node (ref "USB1") (pin "A8") (pinfunction "SBU1_A8") (pintype "passive+no_connect"))
    )
    (net (code "41") (name "unconnected-(USB1-SBU2-PadB8)") (class "Default")
      (node (ref "USB1") (pin "B8") (pinfunction "SBU2_B8") (pintype "passive+no_connect"))
    )
    (net (code "42") (name "unconnected-(USB_5VOUT-D+-Pad3)") (class "Default")
      (node (ref "USB_5VOUT") (pin "3") (pinfunction "D+_3") (pintype "passive+no_connect"))
    )
    (net (code "43") (name "unconnected-(USB_5VOUT-D--Pad2)") (class "Default")
      (node (ref "USB_5VOUT") (pin "2") (pinfunction "D-_2") (pintype "passive+no_connect"))
    )
    (net (code "44") (name "unconnected-(VR1-Pad1)") (class "Default")
      (node (ref "VR1") (pin "1") (pinfunction "1_1") (pintype "passive+no_connect"))
    )
    (net (code "45") (name "unconnected-(VR2-Pad1)") (class "Default")
      (node (ref "VR2") (pin "1") (pinfunction "1_1") (pintype "passive+no_connect"))
    )
  )
)
